# Motherboard.net
KiCad netlist of a schematic drawn in EAGLE
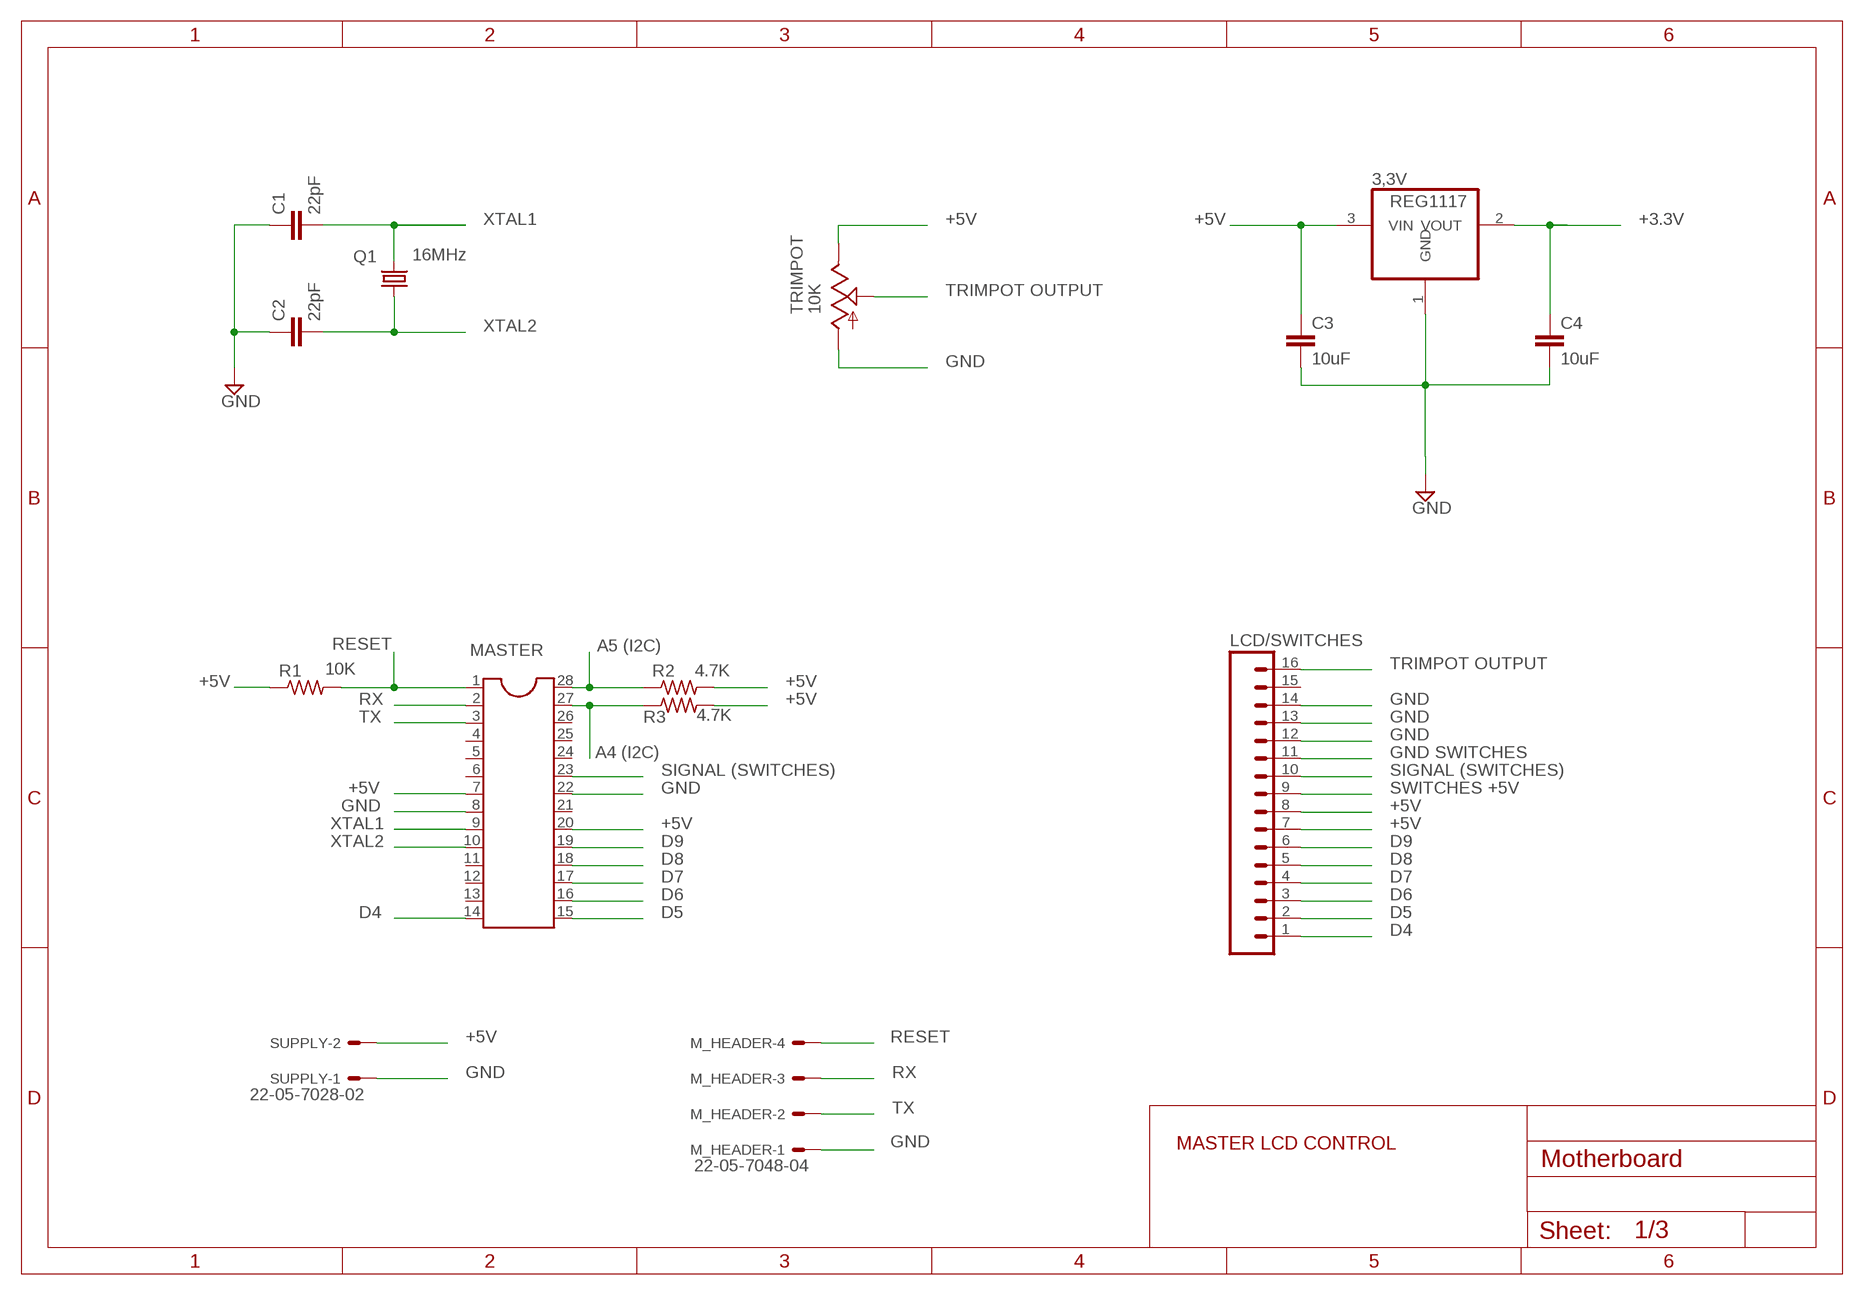
[diagram p0: schematic, sheet 1]
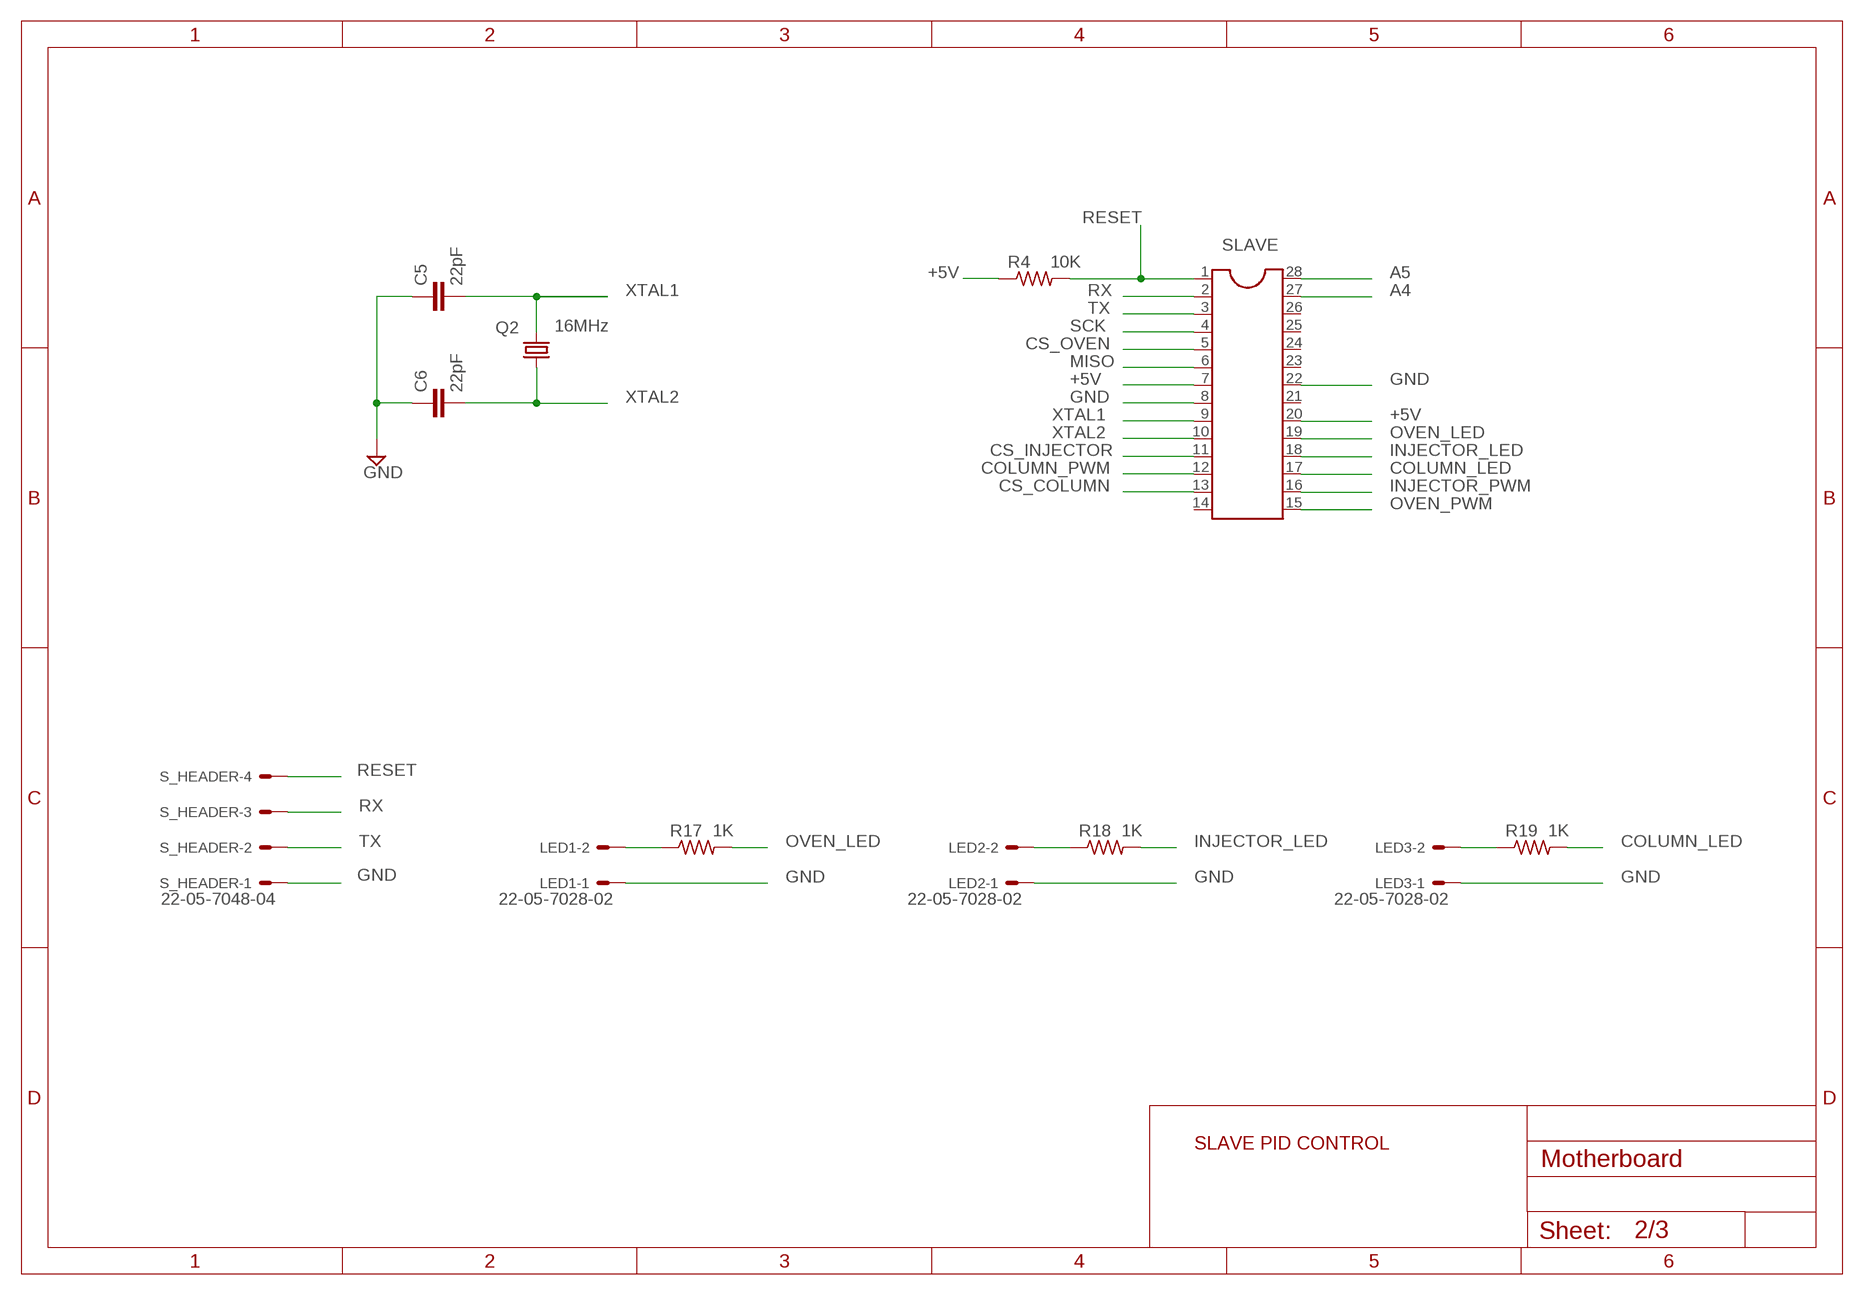
[diagram p1: schematic, sheet 2]
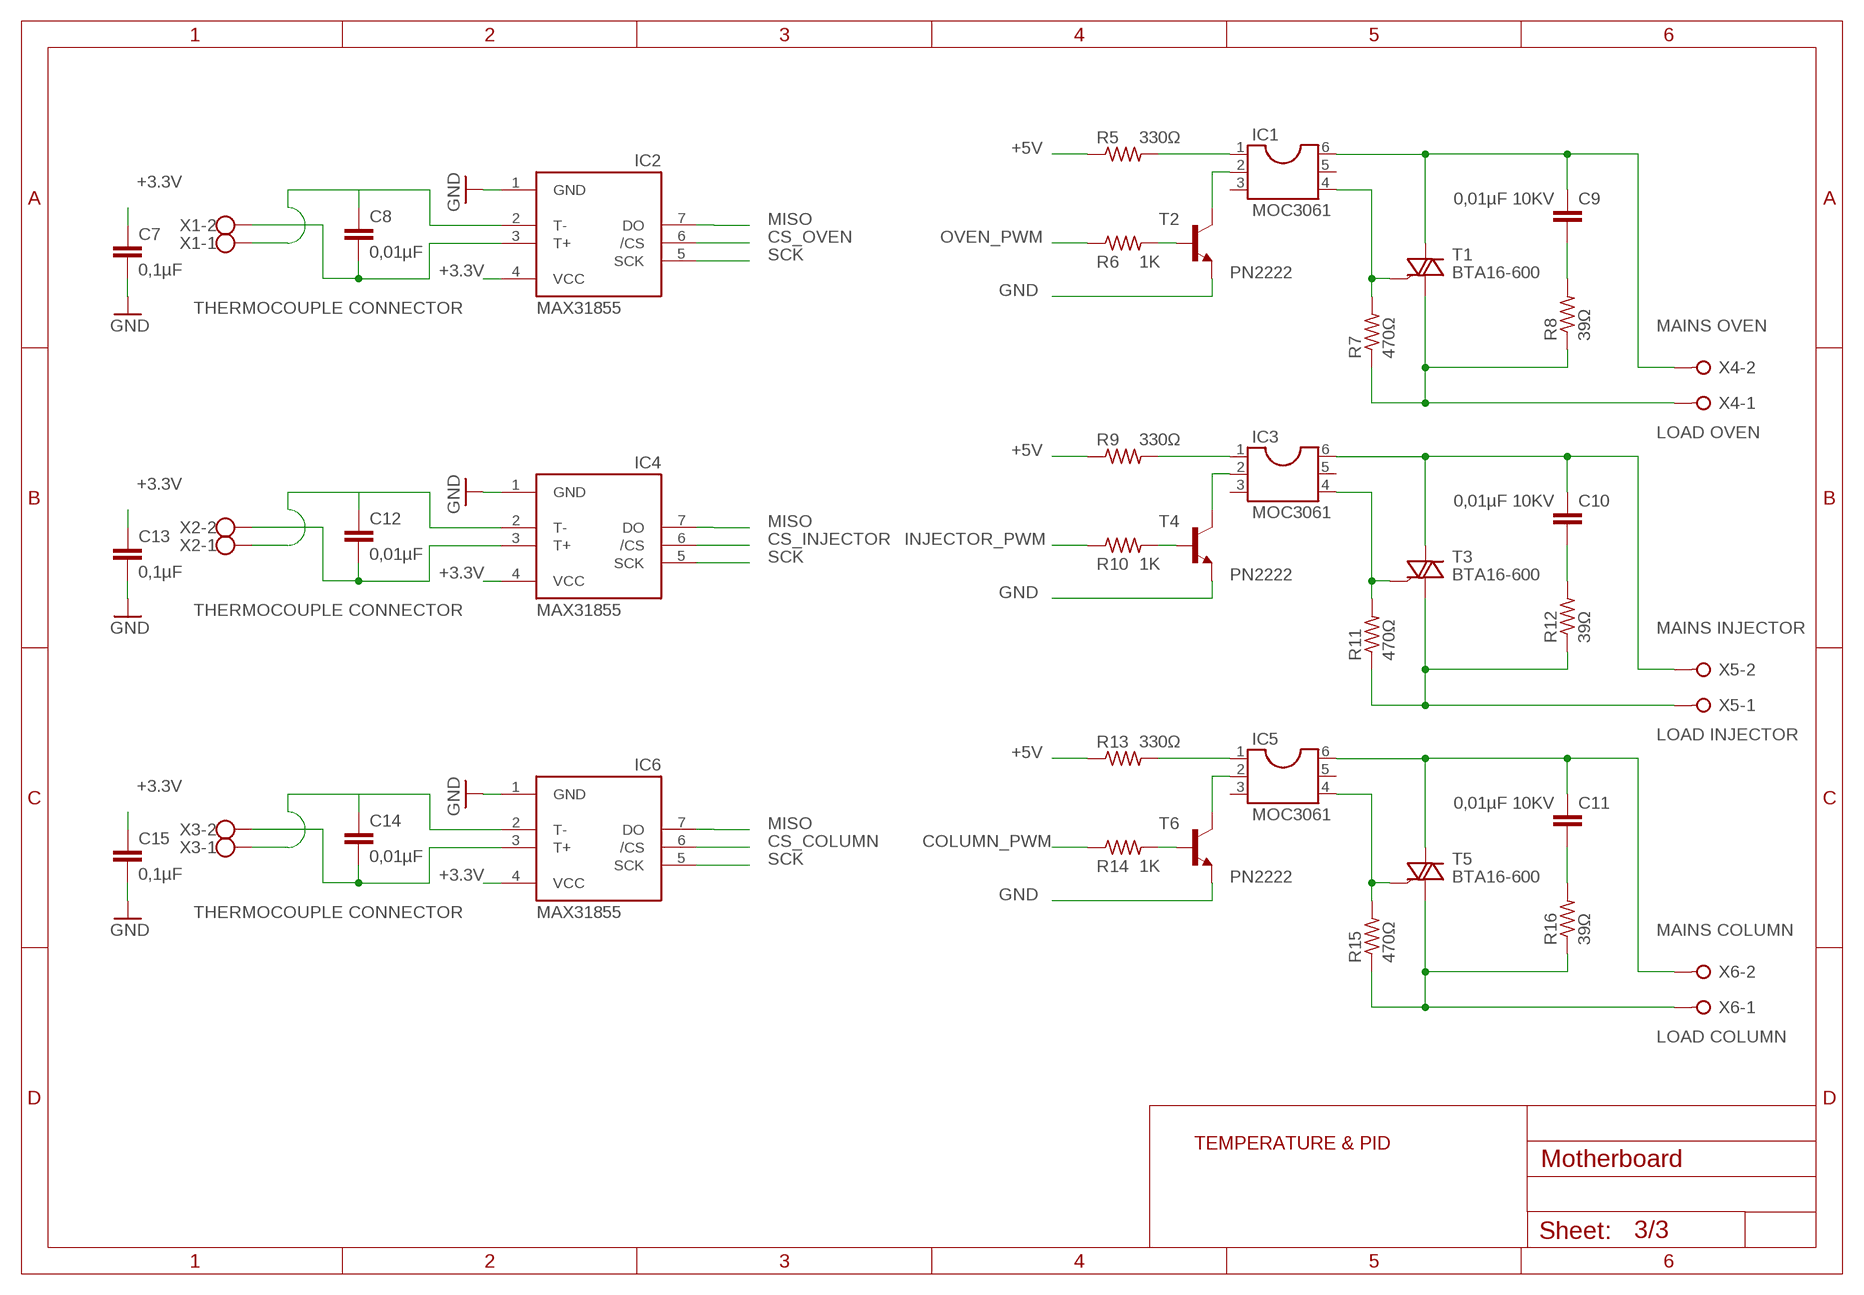
[diagram p2: schematic, sheet 3]

(export (version "E")
  (design (tool "Eeschema 10.0.6"))
  (components
    (comp (ref "C5")
      (value "22pF")
      (footprint "eagle-import:C0805")
      (libsource (lib "eagle-import") (part "C-EUC0805"))
    )
    (comp (ref "C6")
      (value "22pF")
      (footprint "eagle-import:C0805")
      (libsource (lib "eagle-import") (part "C-EUC0805"))
    )
    (comp (ref "LED1")
      (value "22-05-7028-02")
      (footprint "eagle-import:7395-02")
      (libsource (lib "eagle-import") (part "22-?-0205-7028"))
    )
    (comp (ref "LED2")
      (value "22-05-7028-02")
      (footprint "eagle-import:7395-02")
      (libsource (lib "eagle-import") (part "22-?-0205-7028"))
    )
    (comp (ref "LED3")
      (value "22-05-7028-02")
      (footprint "eagle-import:7395-02")
      (libsource (lib "eagle-import") (part "22-?-0205-7028"))
    )
    (comp (ref "Q2")
      (value "16MHz")
      (footprint "eagle-import:HC49_S")
      (libsource (lib "eagle-import") (part "CRYSTALHC49S"))
    )
    (comp (ref "R4")
      (value "10K")
      (footprint "eagle-import:M0805")
      (libsource (lib "eagle-import") (part "R-US_M0805"))
    )
    (comp (ref "R17")
      (value "1K")
      (footprint "eagle-import:M0805")
      (libsource (lib "eagle-import") (part "R-US_M0805"))
    )
    (comp (ref "R18")
      (value "1K")
      (footprint "eagle-import:M0805")
      (libsource (lib "eagle-import") (part "R-US_M0805"))
    )
    (comp (ref "R19")
      (value "1K")
      (footprint "eagle-import:M0805")
      (libsource (lib "eagle-import") (part "R-US_M0805"))
    )
    (comp (ref "SLAVE")
      (value "DIL28-3")
      (footprint "eagle-import:DIL28-3")
      (libsource (lib "eagle-import") (part "DIL28-3"))
    )
    (comp (ref "S_HEADER")
      (value "22-05-7048-04")
      (footprint "eagle-import:7395-04")
      (libsource (lib "eagle-import") (part "22-?-0405-7048"))
    )
    (comp (ref "C7")
      (value "0,1µF")
      (footprint "eagle-import:C0805")
      (libsource (lib "eagle-import") (part "C-EUC0805"))
    )
    (comp (ref "C8")
      (value "0,01µF")
      (footprint "eagle-import:C0805")
      (libsource (lib "eagle-import") (part "C-EUC0805"))
    )
    (comp (ref "C9")
      (value "0,01µF 10KV")
      (footprint "eagle-import:C050-025X075")
      (libsource (lib "eagle-import") (part "C-EU050-025X075"))
    )
    (comp (ref "C10")
      (value "0,01µF 10KV")
      (footprint "eagle-import:C050-025X075")
      (libsource (lib "eagle-import") (part "C-EU050-025X075"))
    )
    (comp (ref "C11")
      (value "0,01µF 10KV")
      (footprint "eagle-import:C050-025X075")
      (libsource (lib "eagle-import") (part "C-EU050-025X075"))
    )
    (comp (ref "C12")
      (value "0,01µF")
      (footprint "eagle-import:C0805")
      (libsource (lib "eagle-import") (part "C-EUC0805"))
    )
    (comp (ref "C13")
      (value "0,1µF")
      (footprint "eagle-import:C0805")
      (libsource (lib "eagle-import") (part "C-EUC0805"))
    )
    (comp (ref "C14")
      (value "0,01µF")
      (footprint "eagle-import:C0805")
      (libsource (lib "eagle-import") (part "C-EUC0805"))
    )
    (comp (ref "C15")
      (value "0,1µF")
      (footprint "eagle-import:C0805")
      (libsource (lib "eagle-import") (part "C-EUC0805"))
    )
    (comp (ref "IC1")
      (value "MOC3061")
      (footprint "eagle-import:SOCKET-06")
      (libsource (lib "eagle-import") (part "DIL6S"))
    )
    (comp (ref "IC2")
      (value "MAX31855")
      (footprint "eagle-import:SO08")
      (libsource (lib "eagle-import") (part "MAX6675"))
    )
    (comp (ref "IC3")
      (value "MOC3061")
      (footprint "eagle-import:SOCKET-06")
      (libsource (lib "eagle-import") (part "DIL6S"))
    )
    (comp (ref "IC4")
      (value "MAX31855")
      (footprint "eagle-import:SO08")
      (libsource (lib "eagle-import") (part "MAX6675"))
    )
    (comp (ref "IC5")
      (value "MOC3061")
      (footprint "eagle-import:SOCKET-06")
      (libsource (lib "eagle-import") (part "DIL6S"))
    )
    (comp (ref "IC6")
      (value "MAX31855")
      (footprint "eagle-import:SO08")
      (libsource (lib "eagle-import") (part "MAX6675"))
    )
    (comp (ref "R5")
      (value "330Ω")
      (footprint "eagle-import:M0805")
      (libsource (lib "eagle-import") (part "R-US_M0805"))
    )
    (comp (ref "R6")
      (value "1K")
      (footprint "eagle-import:M0805")
      (libsource (lib "eagle-import") (part "R-US_M0805"))
    )
    (comp (ref "R7")
      (value "470Ω")
      (footprint "eagle-import:0207_10")
      (libsource (lib "eagle-import") (part "R-US_0207/10"))
    )
    (comp (ref "R8")
      (value "39Ω")
      (footprint "eagle-import:0207_10")
      (libsource (lib "eagle-import") (part "R-US_0207/10"))
    )
    (comp (ref "R9")
      (value "330Ω")
      (footprint "eagle-import:M0805")
      (libsource (lib "eagle-import") (part "R-US_M0805"))
    )
    (comp (ref "R10")
      (value "1K")
      (footprint "eagle-import:M0805")
      (libsource (lib "eagle-import") (part "R-US_M0805"))
    )
    (comp (ref "R11")
      (value "470Ω")
      (footprint "eagle-import:0207_10")
      (libsource (lib "eagle-import") (part "R-US_0207/10"))
    )
    (comp (ref "R12")
      (value "39Ω")
      (footprint "eagle-import:0207_10")
      (libsource (lib "eagle-import") (part "R-US_0207/10"))
    )
    (comp (ref "R13")
      (value "330Ω")
      (footprint "eagle-import:M0805")
      (libsource (lib "eagle-import") (part "R-US_M0805"))
    )
    (comp (ref "R14")
      (value "1K")
      (footprint "eagle-import:M0805")
      (libsource (lib "eagle-import") (part "R-US_M0805"))
    )
    (comp (ref "R15")
      (value "470Ω")
      (footprint "eagle-import:0207_10")
      (libsource (lib "eagle-import") (part "R-US_0207/10"))
    )
    (comp (ref "R16")
      (value "39Ω")
      (footprint "eagle-import:0207_10")
      (libsource (lib "eagle-import") (part "R-US_0207/10"))
    )
    (comp (ref "T1")
      (value "BTA16-600")
      (footprint "eagle-import:TO220BV")
      (libsource (lib "eagle-import") (part "BT138-V"))
    )
    (comp (ref "T2")
      (value "PN2222")
      (footprint "eagle-import:TO92-EBC")
      (libsource (lib "eagle-import") (part "-NPN-TO92-EBC"))
    )
    (comp (ref "T3")
      (value "BTA16-600")
      (footprint "eagle-import:TO220BV")
      (libsource (lib "eagle-import") (part "BT138-V"))
    )
    (comp (ref "T4")
      (value "PN2222")
      (footprint "eagle-import:TO92-EBC")
      (libsource (lib "eagle-import") (part "-NPN-TO92-EBC"))
    )
    (comp (ref "T5")
      (value "BTA16-600")
      (footprint "eagle-import:TO220BV")
      (libsource (lib "eagle-import") (part "BT138-V"))
    )
    (comp (ref "T6")
      (value "PN2222")
      (footprint "eagle-import:TO92-EBC")
      (libsource (lib "eagle-import") (part "-NPN-TO92-EBC"))
    )
    (comp (ref "X1")
      (value "W237-102")
      (footprint "eagle-import:W237-102")
      (fields (field (name "MPN") "237-102"))
      (libsource (lib "eagle-import") (part "W237-102"))
    )
    (comp (ref "X2")
      (value "W237-102")
      (footprint "eagle-import:W237-102")
      (fields (field (name "MPN") "237-102"))
      (libsource (lib "eagle-import") (part "W237-102"))
    )
    (comp (ref "X3")
      (value "W237-102")
      (footprint "eagle-import:W237-102")
      (fields (field (name "MPN") "237-102"))
      (libsource (lib "eagle-import") (part "W237-102"))
    )
    (comp (ref "X4")
      (value "W237-02P")
      (footprint "eagle-import:W237-132")
      (libsource (lib "eagle-import") (part "W237-02P"))
    )
    (comp (ref "X5")
      (value "W237-02P")
      (footprint "eagle-import:W237-132")
      (libsource (lib "eagle-import") (part "W237-02P"))
    )
    (comp (ref "X6")
      (value "W237-02P")
      (footprint "eagle-import:W237-132")
      (libsource (lib "eagle-import") (part "W237-02P"))
    )
    (comp (ref "3,3V")
      (value "REG1117")
      (footprint "eagle-import:SOT223")
      (libsource (lib "eagle-import") (part "REG1117"))
    )
    (comp (ref "C1")
      (value "22pF")
      (footprint "eagle-import:C0805")
      (libsource (lib "eagle-import") (part "C-EUC0805"))
    )
    (comp (ref "C2")
      (value "22pF")
      (footprint "eagle-import:C0805")
      (libsource (lib "eagle-import") (part "C-EUC0805"))
    )
    (comp (ref "C3")
      (value "10uF")
      (footprint "eagle-import:C0805")
      (libsource (lib "eagle-import") (part "C-EUC0805"))
    )
    (comp (ref "C4")
      (value "10uF")
      (footprint "eagle-import:C0805")
      (libsource (lib "eagle-import") (part "C-EUC0805"))
    )
    (comp (ref "LCD/SWITCHES")
      (value "M16")
      (footprint "eagle-import:16P")
      (libsource (lib "eagle-import") (part "M16"))
    )
    (comp (ref "MASTER")
      (value "MASTER NODE")
      (footprint "eagle-import:DIL28-3")
      (libsource (lib "eagle-import") (part "DIL28-3"))
    )
    (comp (ref "M_HEADER")
      (value "22-05-7048-04")
      (footprint "eagle-import:7395-04")
      (libsource (lib "eagle-import") (part "22-?-0405-7048"))
    )
    (comp (ref "Q1")
      (value "16MHz")
      (footprint "eagle-import:HC49_S")
      (libsource (lib "eagle-import") (part "CRYSTALHC49S"))
    )
    (comp (ref "R1")
      (value "10K")
      (footprint "eagle-import:M0805")
      (libsource (lib "eagle-import") (part "R-US_M0805"))
    )
    (comp (ref "R2")
      (value "4.7K")
      (footprint "eagle-import:M0805")
      (libsource (lib "eagle-import") (part "R-US_M0805"))
    )
    (comp (ref "R3")
      (value "4.7K")
      (footprint "eagle-import:M0805")
      (libsource (lib "eagle-import") (part "R-US_M0805"))
    )
    (comp (ref "SUPPLY")
      (value "22-05-7028-02")
      (footprint "eagle-import:7395-02")
      (libsource (lib "eagle-import") (part "22-?-0205-7028"))
    )
    (comp (ref "TRIMPOT")
      (value "10K")
      (footprint "eagle-import:S64W")
      (libsource (lib "eagle-import") (part "TRIM_US-S64W"))
    )
  )
  (nets
    (net (code "1") (name "+3.3V") (class "Default")
      (node (ref "3,3V") (pin "2") (pinfunction "VOUT_2") (pintype "output"))
      (node (ref "C13") (pin "1") (pinfunction "1_1") (pintype "passive"))
      (node (ref "C15") (pin "1") (pinfunction "1_1") (pintype "passive"))
      (node (ref "C4") (pin "1") (pinfunction "1_1") (pintype "passive"))
      (node (ref "C7") (pin "1") (pinfunction "1_1") (pintype "passive"))
      (node (ref "IC2") (pin "4") (pinfunction "VCC_4") (pintype "power_in"))
      (node (ref "IC4") (pin "4") (pinfunction "VCC_4") (pintype "power_in"))
      (node (ref "IC6") (pin "4") (pinfunction "VCC_4") (pintype "power_in"))
    )
    (net (code "2") (name "+5V") (class "Default")
      (node (ref "3,3V") (pin "3") (pinfunction "VIN_3") (pintype "input"))
      (node (ref "C3") (pin "1") (pinfunction "1_1") (pintype "passive"))
      (node (ref "LCD/SWITCHES") (pin "7") (pinfunction "7_7") (pintype "passive"))
      (node (ref "LCD/SWITCHES") (pin "8") (pinfunction "8_8") (pintype "passive"))
      (node (ref "LCD/SWITCHES") (pin "9") (pinfunction "9_9") (pintype "passive"))
      (node (ref "MASTER") (pin "20") (pinfunction "20_20") (pintype "passive"))
      (node (ref "MASTER") (pin "7") (pinfunction "7_7") (pintype "passive"))
      (node (ref "R1") (pin "1") (pinfunction "1_1") (pintype "passive"))
      (node (ref "R13") (pin "1") (pinfunction "1_1") (pintype "passive"))
      (node (ref "R2") (pin "2") (pinfunction "2_2") (pintype "passive"))
      (node (ref "R3") (pin "2") (pinfunction "2_2") (pintype "passive"))
      (node (ref "R4") (pin "1") (pinfunction "1_1") (pintype "passive"))
      (node (ref "R5") (pin "1") (pinfunction "1_1") (pintype "passive"))
      (node (ref "R9") (pin "1") (pinfunction "1_1") (pintype "passive"))
      (node (ref "SLAVE") (pin "20") (pinfunction "20_20") (pintype "passive"))
      (node (ref "SLAVE") (pin "7") (pinfunction "7_7") (pintype "passive"))
      (node (ref "SUPPLY") (pin "2") (pinfunction "S_2") (pintype "passive"))
      (node (ref "TRIMPOT") (pin "E") (pinfunction "E_E") (pintype "passive"))
    )
    (net (code "3") (name "A4") (class "Default")
      (node (ref "MASTER") (pin "27") (pinfunction "27_27") (pintype "passive"))
      (node (ref "R3") (pin "1") (pinfunction "1_1") (pintype "passive"))
      (node (ref "SLAVE") (pin "27") (pinfunction "27_27") (pintype "passive"))
    )
    (net (code "4") (name "A5") (class "Default")
      (node (ref "MASTER") (pin "28") (pinfunction "28_28") (pintype "passive"))
      (node (ref "R2") (pin "1") (pinfunction "1_1") (pintype "passive"))
      (node (ref "SLAVE") (pin "28") (pinfunction "28_28") (pintype "passive"))
    )
    (net (code "5") (name "COLUMN_LED") (class "Default")
      (node (ref "R19") (pin "2") (pinfunction "2_2") (pintype "passive"))
      (node (ref "SLAVE") (pin "17") (pinfunction "17_17") (pintype "passive"))
    )
    (net (code "6") (name "COLUMN_PWM") (class "Default")
      (node (ref "R14") (pin "1") (pinfunction "1_1") (pintype "passive"))
      (node (ref "SLAVE") (pin "12") (pinfunction "12_12") (pintype "passive"))
    )
    (net (code "7") (name "CS_COLUMN") (class "Default")
      (node (ref "IC6") (pin "6") (pinfunction "/CS_6") (pintype "input"))
      (node (ref "SLAVE") (pin "13") (pinfunction "13_13") (pintype "passive"))
    )
    (net (code "8") (name "CS_INJECTOR") (class "Default")
      (node (ref "IC4") (pin "6") (pinfunction "/CS_6") (pintype "input"))
      (node (ref "SLAVE") (pin "11") (pinfunction "11_11") (pintype "passive"))
    )
    (net (code "9") (name "CS_OVEN") (class "Default")
      (node (ref "IC2") (pin "6") (pinfunction "/CS_6") (pintype "input"))
      (node (ref "SLAVE") (pin "5") (pinfunction "5_5") (pintype "passive"))
    )
    (net (code "10") (name "D4") (class "Default")
      (node (ref "LCD/SWITCHES") (pin "1") (pinfunction "1_1") (pintype "passive"))
      (node (ref "MASTER") (pin "14") (pinfunction "14_14") (pintype "passive"))
    )
    (net (code "11") (name "D5") (class "Default")
      (node (ref "LCD/SWITCHES") (pin "2") (pinfunction "2_2") (pintype "passive"))
      (node (ref "MASTER") (pin "15") (pinfunction "15_15") (pintype "passive"))
    )
    (net (code "12") (name "D6") (class "Default")
      (node (ref "LCD/SWITCHES") (pin "3") (pinfunction "3_3") (pintype "passive"))
      (node (ref "MASTER") (pin "16") (pinfunction "16_16") (pintype "passive"))
    )
    (net (code "13") (name "D7") (class "Default")
      (node (ref "LCD/SWITCHES") (pin "4") (pinfunction "4_4") (pintype "passive"))
      (node (ref "MASTER") (pin "17") (pinfunction "17_17") (pintype "passive"))
    )
    (net (code "14") (name "D8") (class "Default")
      (node (ref "LCD/SWITCHES") (pin "5") (pinfunction "5_5") (pintype "passive"))
      (node (ref "MASTER") (pin "18") (pinfunction "18_18") (pintype "passive"))
    )
    (net (code "15") (name "D9") (class "Default")
      (node (ref "LCD/SWITCHES") (pin "6") (pinfunction "6_6") (pintype "passive"))
      (node (ref "MASTER") (pin "19") (pinfunction "19_19") (pintype "passive"))
    )
    (net (code "16") (name "GND") (class "Default")
      (node (ref "3,3V") (pin "1") (pinfunction "GND_1") (pintype "power_in"))
      (node (ref "C1") (pin "1") (pinfunction "1_1") (pintype "passive"))
      (node (ref "C13") (pin "2") (pinfunction "2_2") (pintype "passive"))
      (node (ref "C15") (pin "2") (pinfunction "2_2") (pintype "passive"))
      (node (ref "C2") (pin "1") (pinfunction "1_1") (pintype "passive"))
      (node (ref "C3") (pin "2") (pinfunction "2_2") (pintype "passive"))
      (node (ref "C4") (pin "2") (pinfunction "2_2") (pintype "passive"))
      (node (ref "C5") (pin "1") (pinfunction "1_1") (pintype "passive"))
      (node (ref "C6") (pin "1") (pinfunction "1_1") (pintype "passive"))
      (node (ref "C7") (pin "2") (pinfunction "2_2") (pintype "passive"))
      (node (ref "IC2") (pin "1") (pinfunction "GND_1") (pintype "power_in"))
      (node (ref "IC4") (pin "1") (pinfunction "GND_1") (pintype "power_in"))
      (node (ref "IC6") (pin "1") (pinfunction "GND_1") (pintype "power_in"))
      (node (ref "LCD/SWITCHES") (pin "11") (pinfunction "11_11") (pintype "passive"))
      (node (ref "LCD/SWITCHES") (pin "12") (pinfunction "12_12") (pintype "passive"))
      (node (ref "LCD/SWITCHES") (pin "13") (pinfunction "13_13") (pintype "passive"))
      (node (ref "LCD/SWITCHES") (pin "14") (pinfunction "14_14") (pintype "passive"))
      (node (ref "LED1") (pin "1") (pinfunction "S_1") (pintype "passive"))
      (node (ref "LED2") (pin "1") (pinfunction "S_1") (pintype "passive"))
      (node (ref "LED3") (pin "1") (pinfunction "S_1") (pintype "passive"))
      (node (ref "MASTER") (pin "22") (pinfunction "22_22") (pintype "passive"))
      (node (ref "MASTER") (pin "8") (pinfunction "8_8") (pintype "passive"))
      (node (ref "M_HEADER") (pin "1") (pinfunction "S_1") (pintype "passive"))
      (node (ref "SLAVE") (pin "22") (pinfunction "22_22") (pintype "passive"))
      (node (ref "SLAVE") (pin "8") (pinfunction "8_8") (pintype "passive"))
      (node (ref "SUPPLY") (pin "1") (pinfunction "S_1") (pintype "passive"))
      (node (ref "S_HEADER") (pin "1") (pinfunction "S_1") (pintype "passive"))
      (node (ref "T2") (pin "E") (pinfunction "E_E") (pintype "passive"))
      (node (ref "T4") (pin "E") (pinfunction "E_E") (pintype "passive"))
      (node (ref "T6") (pin "E") (pinfunction "E_E") (pintype "passive"))
      (node (ref "TRIMPOT") (pin "A") (pinfunction "A_A") (pintype "passive"))
    )
    (net (code "17") (name "INJECTOR_LED") (class "Default")
      (node (ref "R18") (pin "2") (pinfunction "2_2") (pintype "passive"))
      (node (ref "SLAVE") (pin "18") (pinfunction "18_18") (pintype "passive"))
    )
    (net (code "18") (name "INJECTOR_PWM") (class "Default")
      (node (ref "R10") (pin "1") (pinfunction "1_1") (pintype "passive"))
      (node (ref "SLAVE") (pin "16") (pinfunction "16_16") (pintype "passive"))
    )
    (net (code "19") (name "MISO") (class "Default")
      (node (ref "IC2") (pin "7") (pinfunction "DO_7") (pintype "output"))
      (node (ref "IC4") (pin "7") (pinfunction "DO_7") (pintype "output"))
      (node (ref "IC6") (pin "7") (pinfunction "DO_7") (pintype "output"))
      (node (ref "SLAVE") (pin "6") (pinfunction "6_6") (pintype "passive"))
    )
    (net (code "20") (name "Net-(C9-Pad2)") (class "Default")
      (node (ref "C9") (pin "2") (pinfunction "2_2") (pintype "passive"))
      (node (ref "R8") (pin "2") (pinfunction "2_2") (pintype "passive"))
    )
    (net (code "21") (name "Net-(C10-Pad2)") (class "Default")
      (node (ref "C10") (pin "2") (pinfunction "2_2") (pintype "passive"))
      (node (ref "R12") (pin "2") (pinfunction "2_2") (pintype "passive"))
    )
    (net (code "22") (name "Net-(C11-Pad2)") (class "Default")
      (node (ref "C11") (pin "2") (pinfunction "2_2") (pintype "passive"))
      (node (ref "R16") (pin "2") (pinfunction "2_2") (pintype "passive"))
    )
    (net (code "23") (name "Net-(IC1-Pad1)") (class "Default")
      (node (ref "IC1") (pin "1") (pinfunction "1_1") (pintype "passive"))
      (node (ref "R5") (pin "2") (pinfunction "2_2") (pintype "passive"))
    )
    (net (code "24") (name "Net-(IC1-Pad2)") (class "Default")
      (node (ref "IC1") (pin "2") (pinfunction "2_2") (pintype "passive"))
      (node (ref "T2") (pin "C") (pinfunction "C_C") (pintype "passive"))
    )
    (net (code "25") (name "Net-(IC1-Pad4)") (class "Default")
      (node (ref "IC1") (pin "4") (pinfunction "4_4") (pintype "passive"))
      (node (ref "R7") (pin "2") (pinfunction "2_2") (pintype "passive"))
      (node (ref "T1") (pin "G") (pinfunction "G_G") (pintype "passive"))
    )
    (net (code "26") (name "Net-(IC2-T+)") (class "Default")
      (node (ref "C8") (pin "2") (pinfunction "2_2") (pintype "passive"))
      (node (ref "IC2") (pin "3") (pinfunction "T+_3") (pintype "input"))
      (node (ref "X1") (pin "2") (pinfunction "KL_2") (pintype "passive"))
    )
    (net (code "27") (name "Net-(IC2-T-)") (class "Default")
      (node (ref "C8") (pin "1") (pinfunction "1_1") (pintype "passive"))
      (node (ref "IC2") (pin "2") (pinfunction "T-_2") (pintype "input"))
      (node (ref "X1") (pin "1") (pinfunction "KL_1") (pintype "passive"))
    )
    (net (code "28") (name "Net-(IC3-Pad1)") (class "Default")
      (node (ref "IC3") (pin "1") (pinfunction "1_1") (pintype "passive"))
      (node (ref "R9") (pin "2") (pinfunction "2_2") (pintype "passive"))
    )
    (net (code "29") (name "Net-(IC3-Pad2)") (class "Default")
      (node (ref "IC3") (pin "2") (pinfunction "2_2") (pintype "passive"))
      (node (ref "T4") (pin "C") (pinfunction "C_C") (pintype "passive"))
    )
    (net (code "30") (name "Net-(IC3-Pad4)") (class "Default")
      (node (ref "IC3") (pin "4") (pinfunction "4_4") (pintype "passive"))
      (node (ref "R11") (pin "2") (pinfunction "2_2") (pintype "passive"))
      (node (ref "T3") (pin "G") (pinfunction "G_G") (pintype "passive"))
    )
    (net (code "31") (name "Net-(IC4-T+)") (class "Default")
      (node (ref "C12") (pin "2") (pinfunction "2_2") (pintype "passive"))
      (node (ref "IC4") (pin "3") (pinfunction "T+_3") (pintype "input"))
      (node (ref "X2") (pin "2") (pinfunction "KL_2") (pintype "passive"))
    )
    (net (code "32") (name "Net-(IC4-T-)") (class "Default")
      (node (ref "C12") (pin "1") (pinfunction "1_1") (pintype "passive"))
      (node (ref "IC4") (pin "2") (pinfunction "T-_2") (pintype "input"))
      (node (ref "X2") (pin "1") (pinfunction "KL_1") (pintype "passive"))
    )
    (net (code "33") (name "Net-(IC5-Pad1)") (class "Default")
      (node (ref "IC5") (pin "1") (pinfunction "1_1") (pintype "passive"))
      (node (ref "R13") (pin "2") (pinfunction "2_2") (pintype "passive"))
    )
    (net (code "34") (name "Net-(IC5-Pad2)") (class "Default")
      (node (ref "IC5") (pin "2") (pinfunction "2_2") (pintype "passive"))
      (node (ref "T6") (pin "C") (pinfunction "C_C") (pintype "passive"))
    )
    (net (code "35") (name "Net-(IC5-Pad4)") (class "Default")
      (node (ref "IC5") (pin "4") (pinfunction "4_4") (pintype "passive"))
      (node (ref "R15") (pin "2") (pinfunction "2_2") (pintype "passive"))
      (node (ref "T5") (pin "G") (pinfunction "G_G") (pintype "passive"))
    )
    (net (code "36") (name "Net-(IC6-T+)") (class "Default")
      (node (ref "C14") (pin "2") (pinfunction "2_2") (pintype "passive"))
      (node (ref "IC6") (pin "3") (pinfunction "T+_3") (pintype "input"))
      (node (ref "X3") (pin "2") (pinfunction "KL_2") (pintype "passive"))
    )
    (net (code "37") (name "Net-(IC6-T-)") (class "Default")
      (node (ref "C14") (pin "1") (pinfunction "1_1") (pintype "passive"))
      (node (ref "IC6") (pin "2") (pinfunction "T-_2") (pintype "input"))
      (node (ref "X3") (pin "1") (pinfunction "KL_1") (pintype "passive"))
    )
    (net (code "38") (name "Net-(LED1B-S)") (class "Default")
      (node (ref "LED1") (pin "2") (pinfunction "S_2") (pintype "passive"))
      (node (ref "R17") (pin "1") (pinfunction "1_1") (pintype "passive"))
    )
    (net (code "39") (name "Net-(LED2B-S)") (class "Default")
      (node (ref "LED2") (pin "2") (pinfunction "S_2") (pintype "passive"))
      (node (ref "R18") (pin "1") (pinfunction "1_1") (pintype "passive"))
    )
    (net (code "40") (name "Net-(LED3B-S)") (class "Default")
      (node (ref "LED3") (pin "2") (pinfunction "S_2") (pintype "passive"))
      (node (ref "R19") (pin "1") (pinfunction "1_1") (pintype "passive"))
    )
    (net (code "41") (name "Net-(R6-Pad2)") (class "Default")
      (node (ref "R6") (pin "2") (pinfunction "2_2") (pintype "passive"))
      (node (ref "T2") (pin "B") (pinfunction "B_B") (pintype "passive"))
    )
    (net (code "42") (name "Net-(R10-Pad2)") (class "Default")
      (node (ref "R10") (pin "2") (pinfunction "2_2") (pintype "passive"))
      (node (ref "T4") (pin "B") (pinfunction "B_B") (pintype "passive"))
    )
    (net (code "43") (name "Net-(R14-Pad2)") (class "Default")
      (node (ref "R14") (pin "2") (pinfunction "2_2") (pintype "passive"))
      (node (ref "T6") (pin "B") (pinfunction "B_B") (pintype "passive"))
    )
    (net (code "44") (name "Net-(T1-A1)") (class "Default")
      (node (ref "R7") (pin "1") (pinfunction "1_1") (pintype "passive"))
      (node (ref "R8") (pin "1") (pinfunction "1_1") (pintype "passive"))
      (node (ref "T1") (pin "T1") (pinfunction "A1_T1") (pintype "passive"))
      (node (ref "X4") (pin "1") (pinfunction "KL_1") (pintype "passive"))
    )
    (net (code "45") (name "Net-(T1-A2)") (class "Default")
      (node (ref "C9") (pin "1") (pinfunction "1_1") (pintype "passive"))
      (node (ref "IC1") (pin "6") (pinfunction "6_6") (pintype "passive"))
      (node (ref "T1") (pin "T2") (pinfunction "A2_T2") (pintype "passive"))
      (node (ref "X4") (pin "2") (pinfunction "KL_2") (pintype "passive"))
    )
    (net (code "46") (name "Net-(T3-A1)") (class "Default")
      (node (ref "R11") (pin "1") (pinfunction "1_1") (pintype "passive"))
      (node (ref "R12") (pin "1") (pinfunction "1_1") (pintype "passive"))
      (node (ref "T3") (pin "T1") (pinfunction "A1_T1") (pintype "passive"))
      (node (ref "X5") (pin "1") (pinfunction "KL_1") (pintype "passive"))
    )
    (net (code "47") (name "Net-(T3-A2)") (class "Default")
      (node (ref "C10") (pin "1") (pinfunction "1_1") (pintype "passive"))
      (node (ref "IC3") (pin "6") (pinfunction "6_6") (pintype "passive"))
      (node (ref "T3") (pin "T2") (pinfunction "A2_T2") (pintype "passive"))
      (node (ref "X5") (pin "2") (pinfunction "KL_2") (pintype "passive"))
    )
    (net (code "48") (name "Net-(T5-A1)") (class "Default")
      (node (ref "R15") (pin "1") (pinfunction "1_1") (pintype "passive"))
      (node (ref "R16") (pin "1") (pinfunction "1_1") (pintype "passive"))
      (node (ref "T5") (pin "T1") (pinfunction "A1_T1") (pintype "passive"))
      (node (ref "X6") (pin "1") (pinfunction "KL_1") (pintype "passive"))
    )
    (net (code "49") (name "Net-(T5-A2)") (class "Default")
      (node (ref "C11") (pin "1") (pinfunction "1_1") (pintype "passive"))
      (node (ref "IC5") (pin "6") (pinfunction "6_6") (pintype "passive"))
      (node (ref "T5") (pin "T2") (pinfunction "A2_T2") (pintype "passive"))
      (node (ref "X6") (pin "2") (pinfunction "KL_2") (pintype "passive"))
    )
    (net (code "50") (name "OVEN_LED") (class "Default")
      (node (ref "R17") (pin "2") (pinfunction "2_2") (pintype "passive"))
      (node (ref "SLAVE") (pin "19") (pinfunction "19_19") (pintype "passive"))
    )
    (net (code "51") (name "OVEN_PWM") (class "Default")
      (node (ref "R6") (pin "1") (pinfunction "1_1") (pintype "passive"))
      (node (ref "SLAVE") (pin "15") (pinfunction "15_15") (pintype "passive"))
    )
    (net (code "52") (name "RESET") (class "Default")
      (node (ref "MASTER") (pin "1") (pinfunction "1_1") (pintype "passive"))
      (node (ref "M_HEADER") (pin "4") (pinfunction "S_4") (pintype "passive"))
      (node (ref "R1") (pin "2") (pinfunction "2_2") (pintype "passive"))
    )
    (net (code "53") (name "RESET_SLAVE") (class "Default")
      (node (ref "R4") (pin "2") (pinfunction "2_2") (pintype "passive"))
      (node (ref "SLAVE") (pin "1") (pinfunction "1_1") (pintype "passive"))
      (node (ref "S_HEADER") (pin "4") (pinfunction "S_4") (pintype "passive"))
    )
    (net (code "54") (name "RX") (class "Default")
      (node (ref "MASTER") (pin "2") (pinfunction "2_2") (pintype "passive"))
      (node (ref "M_HEADER") (pin "3") (pinfunction "S_3") (pintype "passive"))
    )
    (net (code "55") (name "RX_SLAVE") (class "Default")
      (node (ref "SLAVE") (pin "2") (pinfunction "2_2") (pintype "passive"))
      (node (ref "S_HEADER") (pin "3") (pinfunction "S_3") (pintype "passive"))
    )
    (net (code "56") (name "SCK") (class "Default")
      (node (ref "IC2") (pin "5") (pinfunction "SCK_5") (pintype "input"))
      (node (ref "IC4") (pin "5") (pinfunction "SCK_5") (pintype "input"))
      (node (ref "IC6") (pin "5") (pinfunction "SCK_5") (pintype "input"))
      (node (ref "SLAVE") (pin "4") (pinfunction "4_4") (pintype "passive"))
    )
    (net (code "57") (name "SIGNAL") (class "Default")
      (node (ref "LCD/SWITCHES") (pin "10") (pinfunction "10_10") (pintype "passive"))
      (node (ref "MASTER") (pin "23") (pinfunction "23_23") (pintype "passive"))
    )
    (net (code "58") (name "TRIMPOT_OUTPUT") (class "Default")
      (node (ref "LCD/SWITCHES") (pin "16") (pinfunction "16_16") (pintype "passive"))
      (node (ref "TRIMPOT") (pin "S") (pinfunction "S_S") (pintype "passive"))
    )
    (net (code "59") (name "TX") (class "Default")
      (node (ref "MASTER") (pin "3") (pinfunction "3_3") (pintype "passive"))
      (node (ref "M_HEADER") (pin "2") (pinfunction "S_2") (pintype "passive"))
    )
    (net (code "60") (name "TX_SLAVE") (class "Default")
      (node (ref "SLAVE") (pin "3") (pinfunction "3_3") (pintype "passive"))
      (node (ref "S_HEADER") (pin "2") (pinfunction "S_2") (pintype "passive"))
    )
    (net (code "61") (name "XTAL1") (class "Default")
      (node (ref "C1") (pin "2") (pinfunction "2_2") (pintype "passive"))
      (node (ref "MASTER") (pin "9") (pinfunction "9_9") (pintype "passive"))
      (node (ref "Q1") (pin "2") (pinfunction "2_2") (pintype "passive"))
    )
    (net (code "62") (name "XTAL1_SLAVE") (class "Default")
      (node (ref "C5") (pin "2") (pinfunction "2_2") (pintype "passive"))
      (node (ref "Q2") (pin "2") (pinfunction "2_2") (pintype "passive"))
      (node (ref "SLAVE") (pin "9") (pinfunction "9_9") (pintype "passive"))
    )
    (net (code "63") (name "XTAL2") (class "Default")
      (node (ref "C2") (pin "2") (pinfunction "2_2") (pintype "passive"))
      (node (ref "MASTER") (pin "10") (pinfunction "10_10") (pintype "passive"))
      (node (ref "Q1") (pin "1") (pinfunction "1_1") (pintype "passive"))
    )
    (net (code "64") (name "XTAL2_SLAVE") (class "Default")
      (node (ref "C6") (pin "2") (pinfunction "2_2") (pintype "passive"))
      (node (ref "Q2") (pin "1") (pinfunction "1_1") (pintype "passive"))
      (node (ref "SLAVE") (pin "10") (pinfunction "10_10") (pintype "passive"))
    )
    (net (code "65") (name "unconnected-(IC1-Pad3)") (class "Default")
      (node (ref "IC1") (pin "3") (pinfunction "3_3") (pintype "passive"))
    )
    (net (code "66") (name "unconnected-(IC1-Pad5)") (class "Default")
      (node (ref "IC1") (pin "5") (pinfunction "5_5") (pintype "passive"))
    )
    (net (code "67") (name "unconnected-(IC3-Pad3)") (class "Default")
      (node (ref "IC3") (pin "3") (pinfunction "3_3") (pintype "passive"))
    )
    (net (code "68") (name "unconnected-(IC3-Pad5)") (class "Default")
      (node (ref "IC3") (pin "5") (pinfunction "5_5") (pintype "passive"))
    )
    (net (code "69") (name "unconnected-(IC5-Pad3)") (class "Default")
      (node (ref "IC5") (pin "3") (pinfunction "3_3") (pintype "passive"))
    )
    (net (code "70") (name "unconnected-(IC5-Pad5)") (class "Default")
      (node (ref "IC5") (pin "5") (pinfunction "5_5") (pintype "passive"))
    )
    (net (code "71") (name "unconnected-(LCD/SWITCHES-Pad15)") (class "Default")
      (node (ref "LCD/SWITCHES") (pin "15") (pinfunction "15_15") (pintype "passive"))
    )
    (net (code "72") (name "unconnected-(MASTER-Pad4)") (class "Default")
      (node (ref "MASTER") (pin "4") (pinfunction "4_4") (pintype "passive"))
    )
    (net (code "73") (name "unconnected-(MASTER-Pad5)") (class "Default")
      (node (ref "MASTER") (pin "5") (pinfunction "5_5") (pintype "passive"))
    )
    (net (code "74") (name "unconnected-(MASTER-Pad6)") (class "Default")
      (node (ref "MASTER") (pin "6") (pinfunction "6_6") (pintype "passive"))
    )
    (net (code "75") (name "unconnected-(MASTER-Pad11)") (class "Default")
      (node (ref "MASTER") (pin "11") (pinfunction "11_11") (pintype "passive"))
    )
    (net (code "76") (name "unconnected-(MASTER-Pad12)") (class "Default")
      (node (ref "MASTER") (pin "12") (pinfunction "12_12") (pintype "passive"))
    )
    (net (code "77") (name "unconnected-(MASTER-Pad13)") (class "Default")
      (node (ref "MASTER") (pin "13") (pinfunction "13_13") (pintype "passive"))
    )
    (net (code "78") (name "unconnected-(MASTER-Pad21)") (class "Default")
      (node (ref "MASTER") (pin "21") (pinfunction "21_21") (pintype "passive"))
    )
    (net (code "79") (name "unconnected-(MASTER-Pad24)") (class "Default")
      (node (ref "MASTER") (pin "24") (pinfunction "24_24") (pintype "passive"))
    )
    (net (code "80") (name "unconnected-(MASTER-Pad25)") (class "Default")
      (node (ref "MASTER") (pin "25") (pinfunction "25_25") (pintype "passive"))
    )
    (net (code "81") (name "unconnected-(MASTER-Pad26)") (class "Default")
      (node (ref "MASTER") (pin "26") (pinfunction "26_26") (pintype "passive"))
    )
    (net (code "82") (name "unconnected-(SLAVE-Pad14)") (class "Default")
      (node (ref "SLAVE") (pin "14") (pinfunction "14_14") (pintype "passive"))
    )
    (net (code "83") (name "unconnected-(SLAVE-Pad21)") (class "Default")
      (node (ref "SLAVE") (pin "21") (pinfunction "21_21") (pintype "passive"))
    )
    (net (code "84") (name "unconnected-(SLAVE-Pad23)") (class "Default")
      (node (ref "SLAVE") (pin "23") (pinfunction "23_23") (pintype "passive"))
    )
    (net (code "85") (name "unconnected-(SLAVE-Pad24)") (class "Default")
      (node (ref "SLAVE") (pin "24") (pinfunction "24_24") (pintype "passive"))
    )
    (net (code "86") (name "unconnected-(SLAVE-Pad25)") (class "Default")
      (node (ref "SLAVE") (pin "25") (pinfunction "25_25") (pintype "passive"))
    )
    (net (code "87") (name "unconnected-(SLAVE-Pad26)") (class "Default")
      (node (ref "SLAVE") (pin "26") (pinfunction "26_26") (pintype "passive"))
    )
  )
)
